# Boost_Converter.net
KiCad netlist of a schematic drawn in Altium Designer
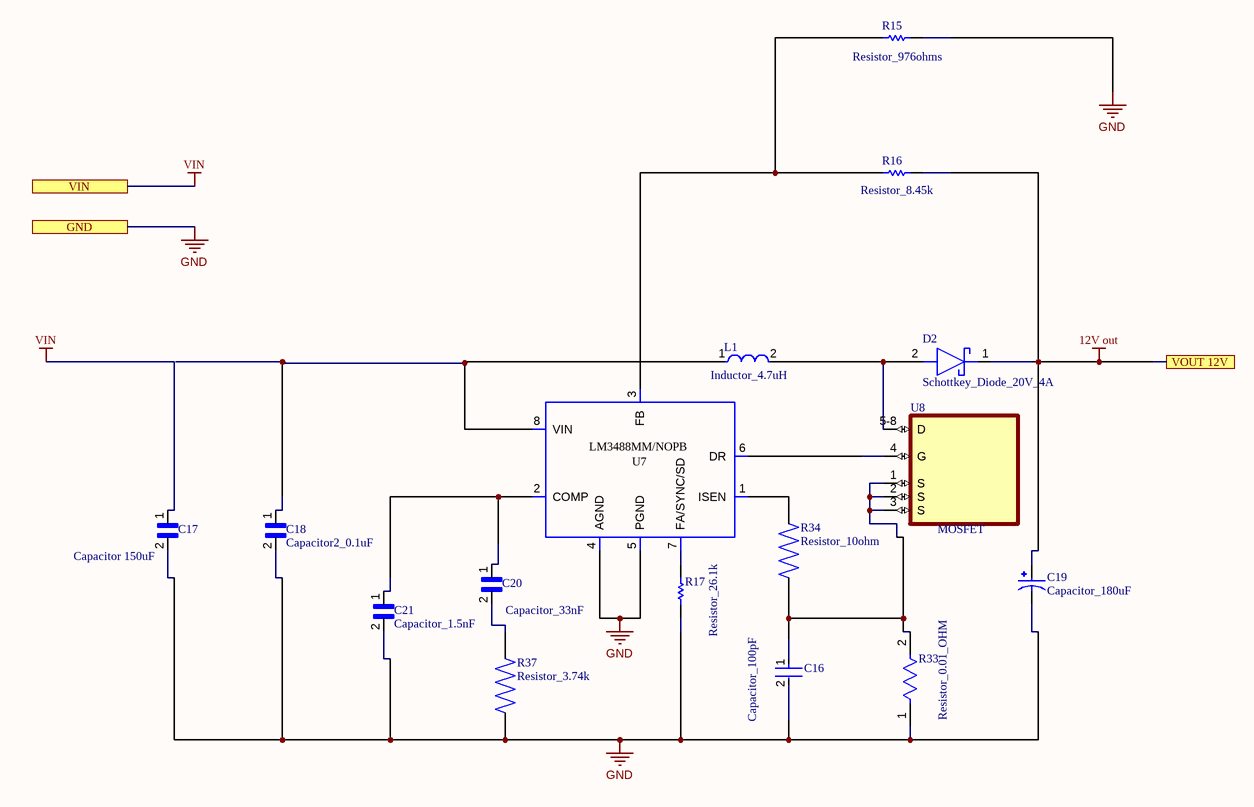
[diagram p0: Boost_Converter.schdoc]

(export (version "E")
  (design (tool "Eeschema 10.0.6"))
  (components
    (comp (ref "C16")
      (value "Capacitor_100pF")
      (footprint "FP-CC0805-0_1-0_7-IPC_A")
      (description "CAP CER 100PF 50V C0G/NPO 0805")
      (fields (field (name "VOLTAGE") "50V") (field (name "TOLERANCE") "5%"))
      (libsource (lib "Altium Content Vault") (part "02cd4be3c70576c341d710602a673aa"))
    )
    (comp (ref "C17")
      (value "Capacitor 150uF")
      (footprint "Capacitor_150uF")
      (description "Multilayer Ceramic Capacitor 150uF 4V 20% 1210 Emboss T/R")
      (fields
        (field (name "MANUFACTURER") "Taiyo Yuden")
        (field (name "MANUFACTURER PART NUMBER") "AMK325ABJ157MM-P")
      )
      (libsource (lib "Schematic_Lib") (part "Capacitor 150uF"))
    )
    (comp (ref "C18")
      (value "Capacitor2_0.1uF")
      (footprint "Capacitor2_0.1uF")
      (description "Cap Ceramic 0.1uF 16V X5R 10% SMD 0402 85°C Paper T/R")
      (fields
        (field (name "MANUFACTURER") "KEMET")
        (field (name "MANUFACTURER PART NUMBER") "C0402C104K4PACTU")
      )
      (libsource (lib "Schematic_Lib") (part "Capacitor2_0.1uF"))
    )
    (comp (ref "C19")
      (value "Capacitor_180uF")
      (footprint "Capacitor_180uF")
      (description "Cap Aluminum Polymer 180uF 20VDC 20%( 8 X 6.9mm) SMD 0.025 Ohm 3200mA 5000h 105C T/R")
      (fields
        (field (name "MANUFACTURER") "Panasonic")
        (field (name "MANUFACTURER PART NUMBER") "20SVPF180M")
      )
      (libsource (lib "Schematic_Lib") (part "Capacitor_180uF"))
    )
    (comp (ref "C20")
      (value "Capacitor_33nF")
      (footprint "Capacitor_33nF")
      (description "TDK - CGA4J2C0G1H333J125AA. - CAP 0.033UF 50V C0G +/-5% SMD 0805")
      (fields
        (field (name "MANUFACTURER") "TDK")
        (field (name "MANUFACTURER PART NUMBER") "CGA4J2C0G1H333J125AA")
      )
      (libsource (lib "Schematic_Lib") (part "Capacitor_33nF"))
    )
    (comp (ref "C21")
      (value "Capacitor_1.5nF")
      (footprint "Capacitor_1.5nF")
      (description "1.5 nF ±5% 50V Ceramic Capacitor C0G, NP0 0805 (2012 Metric)")
      (fields
        (field (name "MANUFACTURER") "TDK")
        (field (name "MANUFACTURER PART NUMBER") "C2012C0G1H152J060AA")
      )
      (libsource (lib "Schematic_Lib") (part "Capacitor_1.5nF"))
    )
    (comp (ref "D2")
      (value "Schottkey_Diode_20V_4A")
      (footprint "Schottkey Diode_20V_4A")
      (description "SL42 Series 20 V 2 A Surface Mount Schottky Barrier Rectifier - DO-214AB (SMC)")
      (fields
        (field (name "MANUFACTURER") "ON Semiconductor")
        (field (name "MANUFACTURER PART NUMBER") "MBRS320T3")
      )
      (libsource (lib "Schematic_Lib") (part "Schottkey_Diode_20V_4A"))
    )
    (comp (ref "L1")
      (value "Inductor_4.7uH")
      (footprint "FP-IHLP-2525EZ-FP_2_413x3-MFG")
      (description "Commercial Inductors, High Saturation Series 4.7uH 6.5A 30.3mΩ 20%")
      (fields (field (name "TOLERANCE") "20%"))
      (libsource (lib "Altium Content Vault") (part "725321dda6339637d4d059423bc1c3c"))
    )
    (comp (ref "R15")
      (value "Resistor_976ohms")
      (footprint "RESC1609X50X30LL10T20")
      (description "976 Ohms ±1% 0.1W, 1/10W Chip Resistor 0603 (1608 Metric) Automotive AEC-Q200 Thick Film")
      (fields (field (name "PART NUMBER") "CRCW0603976RFKEA") (field (name "MANUFACTURER") "Vishay Dale"))
      (libsource (lib "Altium Content Vault") (part "RES"))
    )
    (comp (ref "R16")
      (value "Resistor_8.45k")
      (footprint "RESC1005X40X25LL05T05")
      (description "8.45 kOhms ±1% 0.063W, 1/16W Chip Resistor 0402 (1005 Metric) Automotive AEC-Q200 Thick Film")
      (fields (field (name "PART NUMBER") "CRCW04028K45FKED") (field (name "MANUFACTURER") "Vishay Dale"))
      (libsource (lib "Altium Content Vault") (part "RES"))
    )
    (comp (ref "R17")
      (value "Resistor_26.1k")
      (footprint "RESC1005X40X25LL05T05")
      (description "26.1 kOhms ±1% 0.063W, 1/16W Chip Resistor 0402 (1005 Metric) Automotive AEC-Q200 Thick Film")
      (fields (field (name "PART NUMBER") "CRCW040226K1FKED") (field (name "MANUFACTURER") "Vishay Dale"))
      (libsource (lib "Altium Content Vault") (part "RES"))
    )
    (comp (ref "R33")
      (value "Resistor_0.01_OHM")
      (footprint "FP-CSR1206-MFG")
      (description "RES 0.01 OHM 1% 1/2W 1206")
      (fields (field (name "TOLERANCE") "1%"))
      (libsource (lib "Altium Content Vault") (part "1029c3af85768c4190bb7ad29bc67b5"))
    )
    (comp (ref "R34")
      (value "Resistor_10ohm")
      (footprint "Resistor_10ohm")
      (description "RES TF 1/10W 10 OHM 1% 0603")
      (fields
        (field (name "MANUFACTURER") "Yageo")
        (field (name "MANUFACTURER PART NUMBER") "RT0603DRE0710RL")
      )
      (libsource (lib "Schematic_Lib") (part "Resistor_10ohm"))
    )
    (comp (ref "R37")
      (value "Resistor_3.74k")
      (footprint "Resistor_3.74k")
      (description "Res Thick Film 0603 3.74K Ohm 1% 1/10W ±100ppm/°C Molded SMD Paper T/R")
      (fields
        (field (name "MANUFACTURER") "Yageo")
        (field (name "MANUFACTURER PART NUMBER") "RC0603FR-073K74L")
      )
      (libsource (lib "Schematic_Lib") (part "Resistor_3.74k"))
    )
    (comp (ref "U7")
      (value "LM3488MM/NOPB")
      (footprint "Boost_Converter_Footprint")
      (fields (field (name "PACKAGEREFERENCE") "LM3488MM/NOPB"))
      (libsource (lib "TI WEBENCH") (part "U1"))
    )
    (comp (ref "U8")
      (value "MOSFET")
      (footprint "MOSFET")
      (description "N沟道 VDS=30V VGS=+10V，-8V ID=14A P=2.7W")
      (fields
        (field (name "MANUFACTURER") "Texas Instruments")
        (field (name "MANUFACTURER PART NUMBER") "CSD17308Q3T")
      )
      (libsource (lib "Schematic_Lib") (part "MOSFET"))
    )
  )
  (nets
    (net (code "1") (name "12V out") (class "Default")
      (node (ref "C19") (pin "1") (pinfunction "1_1") (pintype "passive"))
      (node (ref "D2") (pin "1") (pinfunction "K_1") (pintype "passive"))
      (node (ref "R16") (pin "2") (pinfunction "2_2") (pintype "passive"))
    )
    (net (code "2") (name "GND") (class "Default")
      (node (ref "C16") (pin "2") (pinfunction "2_2") (pintype "passive"))
      (node (ref "C17") (pin "2") (pinfunction "2_2") (pintype "passive"))
      (node (ref "C18") (pin "2") (pinfunction "2_2") (pintype "passive"))
      (node (ref "C19") (pin "2") (pinfunction "2_2") (pintype "passive"))
      (node (ref "C21") (pin "2") (pinfunction "2_2") (pintype "passive"))
      (node (ref "R15") (pin "2") (pinfunction "2_2") (pintype "passive"))
      (node (ref "R17") (pin "1") (pinfunction "1_1") (pintype "passive"))
      (node (ref "R33") (pin "1") (pinfunction "1_1") (pintype "passive"))
      (node (ref "R37") (pin "1") (pinfunction "1_1") (pintype "passive"))
      (node (ref "U7") (pin "4") (pinfunction "AGND_4") (pintype "passive"))
      (node (ref "U7") (pin "5") (pinfunction "PGND_5") (pintype "passive"))
    )
    (net (code "3") (name "Net-(C16-Pad1)") (class "Default")
      (node (ref "C16") (pin "1") (pinfunction "1_1") (pintype "passive"))
      (node (ref "R33") (pin "2") (pinfunction "2_2") (pintype "passive"))
      (node (ref "R34") (pin "1") (pinfunction "1_1") (pintype "passive"))
      (node (ref "U8") (pin "1") (pinfunction "S_1") (pintype "bidirectional"))
      (node (ref "U8") (pin "2") (pinfunction "S_2") (pintype "bidirectional"))
      (node (ref "U8") (pin "3") (pinfunction "S_3") (pintype "bidirectional"))
    )
    (net (code "4") (name "Net-(C20-Pad2)") (class "Default")
      (node (ref "C20") (pin "2") (pinfunction "2_2") (pintype "passive"))
      (node (ref "R37") (pin "2") (pinfunction "2_2") (pintype "passive"))
    )
    (net (code "5") (name "Net-(D2-A)") (class "Default")
      (node (ref "D2") (pin "2") (pinfunction "A_2") (pintype "passive"))
      (node (ref "L1") (pin "2") (pinfunction "2_2") (pintype "passive"))
      (node (ref "U8") (pin "5-8") (pinfunction "D_5-8") (pintype "bidirectional"))
    )
    (net (code "6") (name "Net-(U7-COMP)") (class "Default")
      (node (ref "C20") (pin "1") (pinfunction "1_1") (pintype "passive"))
      (node (ref "C21") (pin "1") (pinfunction "1_1") (pintype "passive"))
      (node (ref "U7") (pin "2") (pinfunction "COMP_2") (pintype "passive"))
    )
    (net (code "7") (name "Net-(U7-DR)") (class "Default")
      (node (ref "U7") (pin "6") (pinfunction "DR_6") (pintype "passive"))
      (node (ref "U8") (pin "4") (pinfunction "G_4") (pintype "bidirectional"))
    )
    (net (code "8") (name "Net-(U7-FA{slash}SYNC{slash}SD)") (class "Default")
      (node (ref "R17") (pin "2") (pinfunction "2_2") (pintype "passive"))
      (node (ref "U7") (pin "7") (pinfunction "FA/SYNC/SD_7") (pintype "passive"))
    )
    (net (code "9") (name "Net-(U7-FB)") (class "Default")
      (node (ref "R15") (pin "1") (pinfunction "1_1") (pintype "passive"))
      (node (ref "R16") (pin "1") (pinfunction "1_1") (pintype "passive"))
      (node (ref "U7") (pin "3") (pinfunction "FB_3") (pintype "passive"))
    )
    (net (code "10") (name "Net-(U7-ISEN)") (class "Default")
      (node (ref "R34") (pin "2") (pinfunction "2_2") (pintype "passive"))
      (node (ref "U7") (pin "1") (pinfunction "ISEN_1") (pintype "passive"))
    )
    (net (code "11") (name "Net-(U7-VIN)") (class "Default")
      (node (ref "C18") (pin "1") (pinfunction "1_1") (pintype "passive"))
      (node (ref "L1") (pin "1") (pinfunction "1_1") (pintype "passive"))
      (node (ref "U7") (pin "8") (pinfunction "VIN_8") (pintype "passive"))
    )
    (net (code "12") (name "VIN") (class "Default")
      (node (ref "C17") (pin "1") (pinfunction "1_1") (pintype "passive"))
    )
  )
)
